# ControlModule.net
KiCad netlist of a schematic drawn in EAGLE
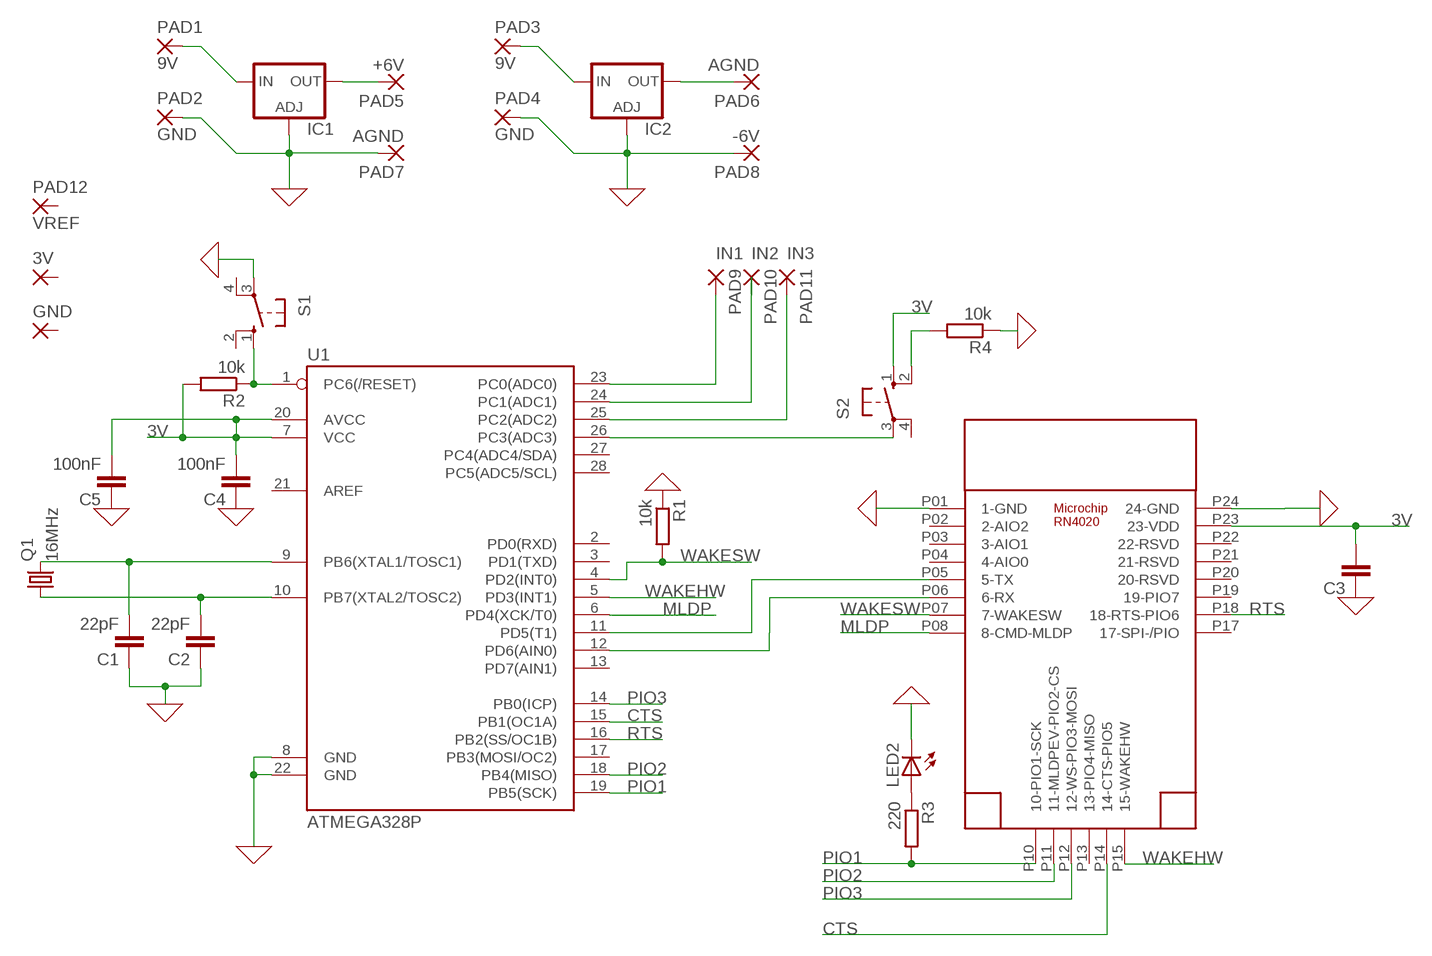
[diagram p0: schematic, sheet 1]

(export (version "E")
  (design (tool "Eeschema 10.0.6"))
  (components
    (comp (ref "3V")
      (value "2,54/1,1")
      (footprint "eagle-import:2,54_1,1")
      (libsource (lib "eagle-import") (part "2,54/1,1"))
    )
    (comp (ref "C1")
      (value "22pF")
      (footprint "eagle-import:C0603")
      (libsource (lib "eagle-import") (part "C-EUC0603"))
    )
    (comp (ref "C2")
      (value "22pF")
      (footprint "eagle-import:C0603")
      (libsource (lib "eagle-import") (part "C-EUC0603"))
    )
    (comp (ref "C3")
      (value "C-EUC0603")
      (footprint "eagle-import:C0603")
      (libsource (lib "eagle-import") (part "C-EUC0603"))
    )
    (comp (ref "C4")
      (value "100nF")
      (footprint "eagle-import:C0603")
      (libsource (lib "eagle-import") (part "C-EUC0603"))
    )
    (comp (ref "C5")
      (value "100nF")
      (footprint "eagle-import:C0603")
      (libsource (lib "eagle-import") (part "C-EUC0603"))
    )
    (comp (ref "GND")
      (value "2,54/1,1")
      (footprint "eagle-import:2,54_1,1")
      (libsource (lib "eagle-import") (part "2,54/1,1"))
    )
    (comp (ref "IC1")
      (value "LM138-TL")
      (footprint "eagle-import:TO220L1")
      (libsource (lib "eagle-import") (part "LM138-TL"))
    )
    (comp (ref "IC2")
      (value "LM138-TL")
      (footprint "eagle-import:TO220L1")
      (libsource (lib "eagle-import") (part "LM138-TL"))
    )
    (comp (ref "LED2")
      (value "LEDCHIPLED_0603")
      (footprint "eagle-import:CHIPLED_0603")
      (libsource (lib "eagle-import") (part "LEDCHIPLED_0603"))
    )
    (comp (ref "PAD1")
      (value "9V")
      (footprint "eagle-import:2,54_1,1")
      (libsource (lib "eagle-import") (part "2,54/1,1"))
    )
    (comp (ref "PAD2")
      (value "GND")
      (footprint "eagle-import:2,54_1,1")
      (libsource (lib "eagle-import") (part "2,54/1,1"))
    )
    (comp (ref "PAD3")
      (value "9V")
      (footprint "eagle-import:2,54_1,1")
      (libsource (lib "eagle-import") (part "2,54/1,1"))
    )
    (comp (ref "PAD4")
      (value "GND")
      (footprint "eagle-import:2,54_1,1")
      (libsource (lib "eagle-import") (part "2,54/1,1"))
    )
    (comp (ref "PAD5")
      (value "+6V")
      (footprint "eagle-import:2,54_1,1")
      (libsource (lib "eagle-import") (part "2,54/1,1"))
    )
    (comp (ref "PAD6")
      (value "AGND")
      (footprint "eagle-import:2,54_1,1")
      (libsource (lib "eagle-import") (part "2,54/1,1"))
    )
    (comp (ref "PAD7")
      (value "AGND")
      (footprint "eagle-import:2,54_1,1")
      (libsource (lib "eagle-import") (part "2,54/1,1"))
    )
    (comp (ref "PAD8")
      (value "-6V")
      (footprint "eagle-import:2,54_1,1")
      (libsource (lib "eagle-import") (part "2,54/1,1"))
    )
    (comp (ref "PAD9")
      (value "2,54/1,1")
      (footprint "eagle-import:2,54_1,1")
      (libsource (lib "eagle-import") (part "2,54/1,1"))
    )
    (comp (ref "PAD10")
      (value "2,54/1,1")
      (footprint "eagle-import:2,54_1,1")
      (libsource (lib "eagle-import") (part "2,54/1,1"))
    )
    (comp (ref "PAD11")
      (value "2,54/1,1")
      (footprint "eagle-import:2,54_1,1")
      (libsource (lib "eagle-import") (part "2,54/1,1"))
    )
    (comp (ref "PAD12")
      (value "VREF")
      (footprint "eagle-import:2,54_1,1")
      (libsource (lib "eagle-import") (part "2,54/1,1"))
    )
    (comp (ref "Q1")
      (value "16MHz")
      (footprint "eagle-import:HC49_S")
      (libsource (lib "eagle-import") (part "CRYSTALHC49S"))
    )
    (comp (ref "R1")
      (value "10k")
      (footprint "eagle-import:R0805")
      (libsource (lib "eagle-import") (part "R-EU_R0805"))
    )
    (comp (ref "R2")
      (value "10k")
      (footprint "eagle-import:R0805")
      (libsource (lib "eagle-import") (part "R-EU_R0805"))
    )
    (comp (ref "R3")
      (value "220")
      (footprint "eagle-import:R0805")
      (libsource (lib "eagle-import") (part "R-EU_R0805"))
    )
    (comp (ref "R4")
      (value "10k")
      (footprint "eagle-import:R0805")
      (libsource (lib "eagle-import") (part "R-EU_R0805"))
    )
    (comp (ref "S1")
      (value "10-XX")
      (footprint "eagle-import:B3F-10XX")
      (fields (field (name "MPN") "B3F-1000"))
      (libsource (lib "eagle-import") (part "10-XX"))
    )
    (comp (ref "S2")
      (value "10-XX")
      (footprint "eagle-import:B3F-10XX")
      (fields (field (name "MPN") "B3F-1000"))
      (libsource (lib "eagle-import") (part "10-XX"))
    )
    (comp (ref "U$1")
      (value "RN4020")
      (footprint "eagle-import:RN4020SMD")
      (libsource (lib "eagle-import") (part "RN4020"))
    )
    (comp (ref "U1")
      (value "ATMEGA328P")
      (footprint "eagle-import:DIP28")
      (libsource (lib "eagle-import") (part "ATMEGA328P_PDIP"))
    )
  )
  (nets
    (net (code "1") (name "/3V") (class "Default")
      (node (ref "C3") (pin "2") (pinfunction "2_2") (pintype "passive"))
      (node (ref "C4") (pin "2") (pinfunction "2_2") (pintype "passive"))
      (node (ref "C5") (pin "2") (pinfunction "2_2") (pintype "passive"))
      (node (ref "R2") (pin "2") (pinfunction "2_2") (pintype "passive"))
      (node (ref "S2") (pin "1") (pinfunction "S_1") (pintype "passive"))
      (node (ref "U$1") (pin "P23") (pinfunction "23-VDD_P23") (pintype "bidirectional"))
      (node (ref "U1") (pin "20") (pinfunction "AVCC_20") (pintype "bidirectional"))
      (node (ref "U1") (pin "7") (pinfunction "VCC_7") (pintype "bidirectional"))
    )
    (net (code "2") (name "/CTS") (class "Default")
      (node (ref "U$1") (pin "P14") (pinfunction "14-CTS-PIO5_P14") (pintype "bidirectional"))
      (node (ref "U1") (pin "15") (pinfunction "PB1(OC1A)_15") (pintype "bidirectional"))
    )
    (net (code "3") (name "/IN1") (class "Default")
      (node (ref "PAD9") (pin "1") (pinfunction "P_1") (pintype "passive"))
      (node (ref "U1") (pin "23") (pinfunction "PC0(ADC0)_23") (pintype "bidirectional"))
    )
    (net (code "4") (name "/IN2") (class "Default")
      (node (ref "PAD10") (pin "1") (pinfunction "P_1") (pintype "passive"))
      (node (ref "U1") (pin "24") (pinfunction "PC1(ADC1)_24") (pintype "bidirectional"))
    )
    (net (code "5") (name "/IN3") (class "Default")
      (node (ref "PAD11") (pin "1") (pinfunction "P_1") (pintype "passive"))
      (node (ref "U1") (pin "25") (pinfunction "PC2(ADC2)_25") (pintype "bidirectional"))
    )
    (net (code "6") (name "/MLDP") (class "Default")
      (node (ref "U$1") (pin "P08") (pinfunction "8-CMD-MLDP_P08") (pintype "bidirectional"))
      (node (ref "U1") (pin "6") (pinfunction "PD4(XCK/T0)_6") (pintype "bidirectional"))
    )
    (net (code "7") (name "/PIO1") (class "Default")
      (node (ref "R3") (pin "2") (pinfunction "2_2") (pintype "passive"))
      (node (ref "U$1") (pin "P10") (pinfunction "10-PIO1-SCK_P10") (pintype "bidirectional"))
      (node (ref "U1") (pin "19") (pinfunction "PB5(SCK)_19") (pintype "bidirectional"))
    )
    (net (code "8") (name "/PIO2") (class "Default")
      (node (ref "U$1") (pin "P11") (pinfunction "11-MLDPEV-PIO2-CS_P11") (pintype "bidirectional"))
      (node (ref "U1") (pin "18") (pinfunction "PB4(MISO)_18") (pintype "bidirectional"))
    )
    (net (code "9") (name "/PIO3") (class "Default")
      (node (ref "U$1") (pin "P12") (pinfunction "12-WS-PIO3-MOSI_P12") (pintype "bidirectional"))
      (node (ref "U1") (pin "14") (pinfunction "PB0(ICP)_14") (pintype "bidirectional"))
    )
    (net (code "10") (name "/RTS") (class "Default")
      (node (ref "U$1") (pin "P18") (pinfunction "18-RTS-PIO6_P18") (pintype "bidirectional"))
      (node (ref "U1") (pin "16") (pinfunction "PB2(SS/OC1B)_16") (pintype "bidirectional"))
    )
    (net (code "11") (name "/WAKEHW") (class "Default")
      (node (ref "U$1") (pin "P15") (pinfunction "15-WAKEHW_P15") (pintype "bidirectional"))
      (node (ref "U1") (pin "5") (pinfunction "PD3(INT1)_5") (pintype "bidirectional"))
    )
    (net (code "12") (name "/WAKESW") (class "Default")
      (node (ref "R1") (pin "2") (pinfunction "2_2") (pintype "passive"))
      (node (ref "U$1") (pin "P07") (pinfunction "7-WAKESW_P07") (pintype "bidirectional"))
      (node (ref "U1") (pin "4") (pinfunction "PD2(INT0)_4") (pintype "bidirectional"))
    )
    (net (code "13") (name "GND") (class "Default")
      (node (ref "C1") (pin "1") (pinfunction "1_1") (pintype "passive"))
      (node (ref "C2") (pin "1") (pinfunction "1_1") (pintype "passive"))
      (node (ref "C3") (pin "1") (pinfunction "1_1") (pintype "passive"))
      (node (ref "C4") (pin "1") (pinfunction "1_1") (pintype "passive"))
      (node (ref "C5") (pin "1") (pinfunction "1_1") (pintype "passive"))
      (node (ref "IC1") (pin "1") (pinfunction "ADJ_1") (pintype "input"))
      (node (ref "IC2") (pin "1") (pinfunction "ADJ_1") (pintype "input"))
      (node (ref "LED2") (pin "C") (pinfunction "C_C") (pintype "passive"))
      (node (ref "PAD2") (pin "1") (pinfunction "P_1") (pintype "passive"))
      (node (ref "PAD4") (pin "1") (pinfunction "P_1") (pintype "passive"))
      (node (ref "PAD7") (pin "1") (pinfunction "P_1") (pintype "passive"))
      (node (ref "PAD8") (pin "1") (pinfunction "P_1") (pintype "passive"))
      (node (ref "R1") (pin "1") (pinfunction "1_1") (pintype "passive"))
      (node (ref "R4") (pin "1") (pinfunction "1_1") (pintype "passive"))
      (node (ref "S1") (pin "3") (pinfunction "P_3") (pintype "passive"))
      (node (ref "U$1") (pin "P01") (pinfunction "1-GND_P01") (pintype "bidirectional"))
      (node (ref "U$1") (pin "P24") (pinfunction "24-GND_P24") (pintype "bidirectional"))
      (node (ref "U1") (pin "22") (pinfunction "GND_22") (pintype "bidirectional"))
      (node (ref "U1") (pin "8") (pinfunction "GND_8") (pintype "bidirectional"))
    )
    (net (code "14") (name "Net-(IC1-IN)") (class "Default")
      (node (ref "IC1") (pin "3") (pinfunction "IN_3") (pintype "input"))
      (node (ref "PAD1") (pin "1") (pinfunction "P_1") (pintype "passive"))
    )
    (net (code "15") (name "Net-(IC1-OUT)") (class "Default")
      (node (ref "IC1") (pin "2") (pinfunction "OUT_2") (pintype "passive"))
      (node (ref "PAD5") (pin "1") (pinfunction "P_1") (pintype "passive"))
    )
    (net (code "16") (name "Net-(IC2-IN)") (class "Default")
      (node (ref "IC2") (pin "3") (pinfunction "IN_3") (pintype "input"))
      (node (ref "PAD3") (pin "1") (pinfunction "P_1") (pintype "passive"))
    )
    (net (code "17") (name "Net-(IC2-OUT)") (class "Default")
      (node (ref "IC2") (pin "2") (pinfunction "OUT_2") (pintype "passive"))
      (node (ref "PAD6") (pin "1") (pinfunction "P_1") (pintype "passive"))
    )
    (net (code "18") (name "Net-(LED2-PadA)") (class "Default")
      (node (ref "LED2") (pin "A") (pinfunction "A_A") (pintype "passive"))
      (node (ref "R3") (pin "1") (pinfunction "1_1") (pintype "passive"))
    )
    (net (code "19") (name "Net-(S1-S)") (class "Default")
      (node (ref "R2") (pin "1") (pinfunction "1_1") (pintype "passive"))
      (node (ref "S1") (pin "1") (pinfunction "S_1") (pintype "passive"))
      (node (ref "U1") (pin "1") (pinfunction "PC6(/RESET)_1") (pintype "bidirectional"))
    )
    (net (code "20") (name "Net-(S2-P)") (class "Default")
      (node (ref "S2") (pin "3") (pinfunction "P_3") (pintype "passive"))
      (node (ref "U1") (pin "26") (pinfunction "PC3(ADC3)_26") (pintype "bidirectional"))
    )
    (net (code "21") (name "Net-(S2-S1)") (class "Default")
      (node (ref "R4") (pin "2") (pinfunction "2_2") (pintype "passive"))
      (node (ref "S2") (pin "2") (pinfunction "S1_2") (pintype "passive"))
    )
    (net (code "22") (name "Net-(U$1-5-TX)") (class "Default")
      (node (ref "U$1") (pin "P05") (pinfunction "5-TX_P05") (pintype "bidirectional"))
      (node (ref "U1") (pin "11") (pinfunction "PD5(T1)_11") (pintype "bidirectional"))
    )
    (net (code "23") (name "Net-(U$1-6-RX)") (class "Default")
      (node (ref "U$1") (pin "P06") (pinfunction "6-RX_P06") (pintype "bidirectional"))
      (node (ref "U1") (pin "12") (pinfunction "PD6(AIN0)_12") (pintype "bidirectional"))
    )
    (net (code "24") (name "Net-(U1-PB6(XTAL1{slash}TOSC1))") (class "Default")
      (node (ref "C1") (pin "2") (pinfunction "2_2") (pintype "passive"))
      (node (ref "Q1") (pin "2") (pinfunction "2_2") (pintype "passive"))
      (node (ref "U1") (pin "9") (pinfunction "PB6(XTAL1/TOSC1)_9") (pintype "bidirectional"))
    )
    (net (code "25") (name "Net-(U1-PB7(XTAL2{slash}TOSC2))") (class "Default")
      (node (ref "C2") (pin "2") (pinfunction "2_2") (pintype "passive"))
      (node (ref "Q1") (pin "1") (pinfunction "1_1") (pintype "passive"))
      (node (ref "U1") (pin "10") (pinfunction "PB7(XTAL2/TOSC2)_10") (pintype "bidirectional"))
    )
    (net (code "26") (name "unconnected-(3V-P-Pad1)") (class "Default")
      (node (ref "3V") (pin "1") (pinfunction "P_1") (pintype "passive"))
    )
    (net (code "27") (name "unconnected-(GND-P-Pad1)") (class "Default")
      (node (ref "GND") (pin "1") (pinfunction "P_1") (pintype "passive"))
    )
    (net (code "28") (name "unconnected-(PAD12-P-Pad1)") (class "Default")
      (node (ref "PAD12") (pin "1") (pinfunction "P_1") (pintype "passive"))
    )
    (net (code "29") (name "unconnected-(S1-P1-Pad4)") (class "Default")
      (node (ref "S1") (pin "4") (pinfunction "P1_4") (pintype "passive"))
    )
    (net (code "30") (name "unconnected-(S1-S1-Pad2)") (class "Default")
      (node (ref "S1") (pin "2") (pinfunction "S1_2") (pintype "passive"))
    )
    (net (code "31") (name "unconnected-(S2-P1-Pad4)") (class "Default")
      (node (ref "S2") (pin "4") (pinfunction "P1_4") (pintype "passive"))
    )
    (net (code "32") (name "unconnected-(U$1-2-AIO2-PadP02)") (class "Default")
      (node (ref "U$1") (pin "P02") (pinfunction "2-AIO2_P02") (pintype "bidirectional"))
    )
    (net (code "33") (name "unconnected-(U$1-3-AIO1-PadP03)") (class "Default")
      (node (ref "U$1") (pin "P03") (pinfunction "3-AIO1_P03") (pintype "bidirectional"))
    )
    (net (code "34") (name "unconnected-(U$1-4-AIO0-PadP04)") (class "Default")
      (node (ref "U$1") (pin "P04") (pinfunction "4-AIO0_P04") (pintype "bidirectional"))
    )
    (net (code "35") (name "unconnected-(U$1-13-PIO4-MISO-PadP13)") (class "Default")
      (node (ref "U$1") (pin "P13") (pinfunction "13-PIO4-MISO_P13") (pintype "bidirectional"))
    )
    (net (code "36") (name "unconnected-(U$1-17-SPI-{slash}PIO-PadP17)") (class "Default")
      (node (ref "U$1") (pin "P17") (pinfunction "17-SPI-/PIO_P17") (pintype "bidirectional"))
    )
    (net (code "37") (name "unconnected-(U$1-19-PIO7-PadP19)") (class "Default")
      (node (ref "U$1") (pin "P19") (pinfunction "19-PIO7_P19") (pintype "bidirectional"))
    )
    (net (code "38") (name "unconnected-(U$1-20-RSVD-PadP20)") (class "Default")
      (node (ref "U$1") (pin "P20") (pinfunction "20-RSVD_P20") (pintype "bidirectional"))
    )
    (net (code "39") (name "unconnected-(U$1-21-RSVD-PadP21)") (class "Default")
      (node (ref "U$1") (pin "P21") (pinfunction "21-RSVD_P21") (pintype "bidirectional"))
    )
    (net (code "40") (name "unconnected-(U$1-22-RSVD-PadP22)") (class "Default")
      (node (ref "U$1") (pin "P22") (pinfunction "22-RSVD_P22") (pintype "bidirectional"))
    )
    (net (code "41") (name "unconnected-(U1-AREF-Pad21)") (class "Default")
      (node (ref "U1") (pin "21") (pinfunction "AREF_21") (pintype "bidirectional"))
    )
    (net (code "42") (name "unconnected-(U1-PB3(MOSI{slash}OC2)-Pad17)") (class "Default")
      (node (ref "U1") (pin "17") (pinfunction "PB3(MOSI/OC2)_17") (pintype "bidirectional"))
    )
    (net (code "43") (name "unconnected-(U1-PC4(ADC4{slash}SDA)-Pad27)") (class "Default")
      (node (ref "U1") (pin "27") (pinfunction "PC4(ADC4/SDA)_27") (pintype "bidirectional"))
    )
    (net (code "44") (name "unconnected-(U1-PC5(ADC5{slash}SCL)-Pad28)") (class "Default")
      (node (ref "U1") (pin "28") (pinfunction "PC5(ADC5/SCL)_28") (pintype "bidirectional"))
    )
    (net (code "45") (name "unconnected-(U1-PD0(RXD)-Pad2)") (class "Default")
      (node (ref "U1") (pin "2") (pinfunction "PD0(RXD)_2") (pintype "bidirectional"))
    )
    (net (code "46") (name "unconnected-(U1-PD1(TXD)-Pad3)") (class "Default")
      (node (ref "U1") (pin "3") (pinfunction "PD1(TXD)_3") (pintype "bidirectional"))
    )
    (net (code "47") (name "unconnected-(U1-PD7(AIN1)-Pad13)") (class "Default")
      (node (ref "U1") (pin "13") (pinfunction "PD7(AIN1)_13") (pintype "bidirectional"))
    )
  )
)
